# Block_Diagram.net
KiCad netlist of a schematic drawn in EAGLE
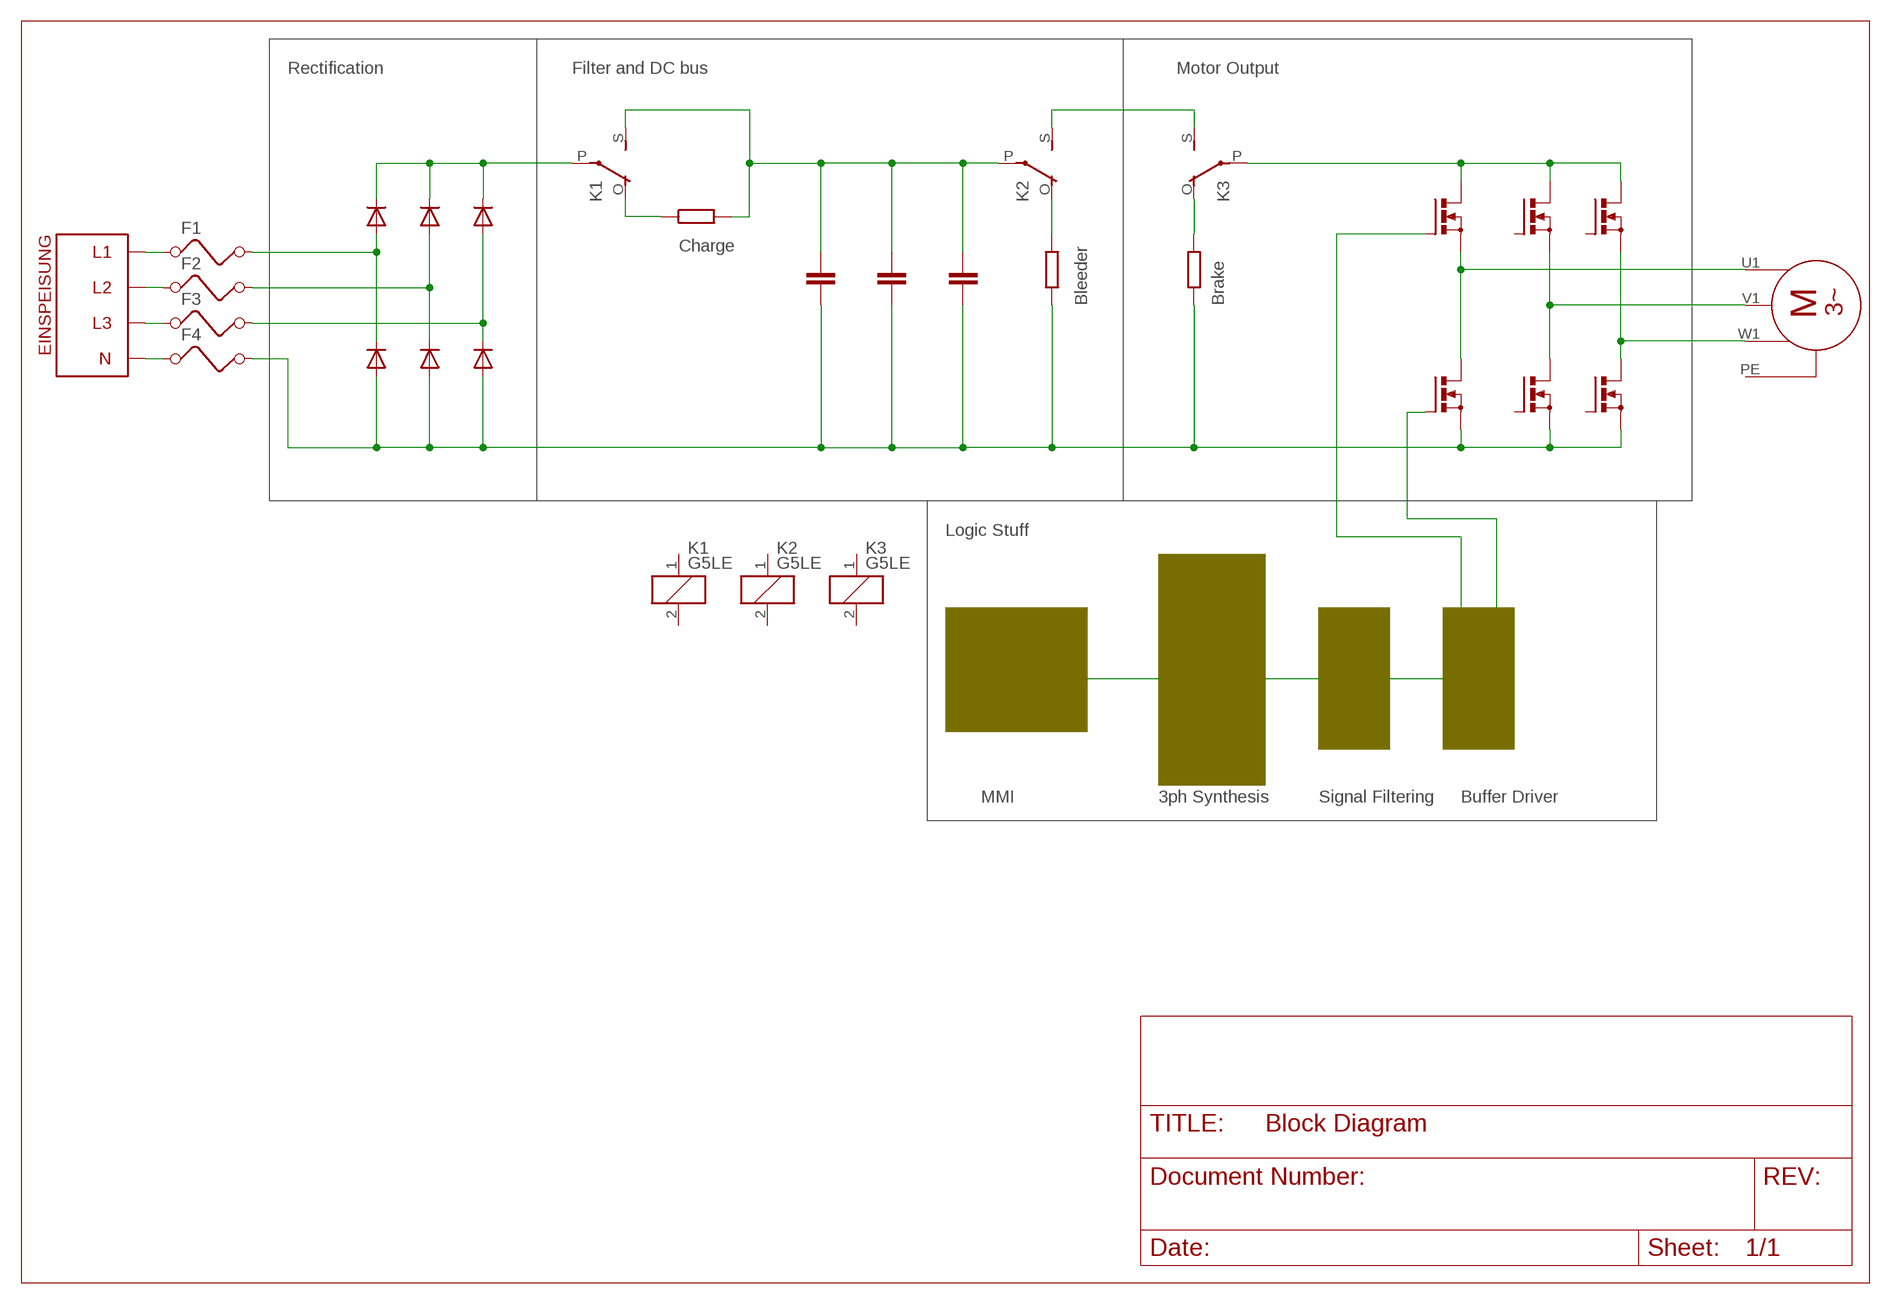
[diagram p0: schematic, sheet 1]

(export (version "E")
  (design (tool "Eeschema 10.0.6"))
  (components
    (comp (ref "F1")
      (value "FUSE")
      (footprint "eagle-import:FUSE")
      (libsource (lib "eagle-import") (part "FUSE"))
    )
    (comp (ref "F2")
      (value "FUSE")
      (footprint "eagle-import:FUSE")
      (libsource (lib "eagle-import") (part "FUSE"))
    )
    (comp (ref "F3")
      (value "FUSE")
      (footprint "eagle-import:FUSE")
      (libsource (lib "eagle-import") (part "FUSE"))
    )
    (comp (ref "F4")
      (value "FUSE")
      (footprint "eagle-import:FUSE")
      (libsource (lib "eagle-import") (part "FUSE"))
    )
    (comp (ref "K1")
      (value "G5LE")
      (footprint "eagle-import:G5LE")
      (libsource (lib "eagle-import") (part "G5LE"))
    )
    (comp (ref "K2")
      (value "G5LE")
      (footprint "eagle-import:G5LE")
      (libsource (lib "eagle-import") (part "G5LE"))
    )
    (comp (ref "K3")
      (value "G5LE")
      (footprint "eagle-import:G5LE")
      (libsource (lib "eagle-import") (part "G5LE"))
    )
    (comp (ref "M1")
      (value "MOTOR_3-POL_PE")
      (footprint "eagle-import:MOTOR_3-POL_PE")
      (libsource (lib "eagle-import") (part "MOTOR_3-POL_PE"))
    )
    (comp (ref "Q1")
      (value "IRF512")
      (footprint "eagle-import:TO220BV")
      (libsource (lib "eagle-import") (part "IRF512"))
    )
    (comp (ref "Q2")
      (value "IRF512")
      (footprint "eagle-import:TO220BV")
      (libsource (lib "eagle-import") (part "IRF512"))
    )
    (comp (ref "Q3")
      (value "IRF512")
      (footprint "eagle-import:TO220BV")
      (libsource (lib "eagle-import") (part "IRF512"))
    )
    (comp (ref "Q4")
      (value "IRF512")
      (footprint "eagle-import:TO220BV")
      (libsource (lib "eagle-import") (part "IRF512"))
    )
    (comp (ref "Q5")
      (value "IRF512")
      (footprint "eagle-import:TO220BV")
      (libsource (lib "eagle-import") (part "IRF512"))
    )
    (comp (ref "Q6")
      (value "IRF512")
      (footprint "eagle-import:TO220BV")
      (libsource (lib "eagle-import") (part "IRF512"))
    )
  )
  (nets
    (net (code "1") (name "Net-(F1-Pad1)") (class "Default")
      (node (ref "F1") (pin "1") (pinfunction "1_1") (pintype "passive"))
    )
    (net (code "2") (name "Net-(F2-Pad1)") (class "Default")
      (node (ref "F2") (pin "1") (pinfunction "1_1") (pintype "passive"))
    )
    (net (code "3") (name "Net-(F3-Pad1)") (class "Default")
      (node (ref "F3") (pin "1") (pinfunction "1_1") (pintype "passive"))
    )
    (net (code "4") (name "Net-(F4-Pad1)") (class "Default")
      (node (ref "F4") (pin "1") (pinfunction "1_1") (pintype "passive"))
    )
    (net (code "5") (name "Net-(F4-Pad2)") (class "Default")
      (node (ref "F4") (pin "2") (pinfunction "2_2") (pintype "passive"))
      (node (ref "Q4") (pin "S") (pinfunction "S_S") (pintype "passive"))
      (node (ref "Q5") (pin "S") (pinfunction "S_S") (pintype "passive"))
      (node (ref "Q6") (pin "S") (pinfunction "S_S") (pintype "passive"))
    )
    (net (code "6") (name "Net-(K1-PadS)") (class "Default")
      (node (ref "K1") (pin "S") (pinfunction "S_S") (pintype "passive"))
      (node (ref "K2") (pin "P") (pinfunction "P_P") (pintype "passive"))
    )
    (net (code "7") (name "Net-(K2-PadS)") (class "Default")
      (node (ref "K2") (pin "S") (pinfunction "S_S") (pintype "passive"))
      (node (ref "K3") (pin "S") (pinfunction "S_S") (pintype "passive"))
    )
    (net (code "8") (name "Net-(K3-PadP)") (class "Default")
      (node (ref "K3") (pin "P") (pinfunction "P_P") (pintype "passive"))
      (node (ref "Q1") (pin "D") (pinfunction "D_D") (pintype "passive"))
      (node (ref "Q2") (pin "D") (pinfunction "D_D") (pintype "passive"))
      (node (ref "Q3") (pin "D") (pinfunction "D_D") (pintype "passive"))
    )
    (net (code "9") (name "Net-(M1-PadU1)") (class "Default")
      (node (ref "M1") (pin "U1") (pinfunction "U1_U1") (pintype "passive"))
      (node (ref "Q1") (pin "S") (pinfunction "S_S") (pintype "passive"))
      (node (ref "Q6") (pin "D") (pinfunction "D_D") (pintype "passive"))
    )
    (net (code "10") (name "Net-(M1-PadV1)") (class "Default")
      (node (ref "M1") (pin "V1") (pinfunction "V1_V1") (pintype "passive"))
      (node (ref "Q2") (pin "S") (pinfunction "S_S") (pintype "passive"))
      (node (ref "Q5") (pin "D") (pinfunction "D_D") (pintype "passive"))
    )
    (net (code "11") (name "Net-(M1-PadW1)") (class "Default")
      (node (ref "M1") (pin "W1") (pinfunction "W1_W1") (pintype "passive"))
      (node (ref "Q3") (pin "S") (pinfunction "S_S") (pintype "passive"))
      (node (ref "Q4") (pin "D") (pinfunction "D_D") (pintype "passive"))
    )
    (net (code "12") (name "unconnected-(F1-Pad2)") (class "Default")
      (node (ref "F1") (pin "2") (pinfunction "2_2") (pintype "passive"))
    )
    (net (code "13") (name "unconnected-(F2-Pad2)") (class "Default")
      (node (ref "F2") (pin "2") (pinfunction "2_2") (pintype "passive"))
    )
    (net (code "14") (name "unconnected-(F3-Pad2)") (class "Default")
      (node (ref "F3") (pin "2") (pinfunction "2_2") (pintype "passive"))
    )
    (net (code "15") (name "unconnected-(K1-Pad1)") (class "Default")
      (node (ref "K1") (pin "1") (pinfunction "1_1") (pintype "passive"))
    )
    (net (code "16") (name "unconnected-(K1-Pad2)") (class "Default")
      (node (ref "K1") (pin "2") (pinfunction "2_2") (pintype "passive"))
    )
    (net (code "17") (name "unconnected-(K1-PadO)") (class "Default")
      (node (ref "K1") (pin "O") (pinfunction "O_O") (pintype "passive"))
    )
    (net (code "18") (name "unconnected-(K1-PadP)") (class "Default")
      (node (ref "K1") (pin "P") (pinfunction "P_P") (pintype "passive"))
    )
    (net (code "19") (name "unconnected-(K2-Pad1)") (class "Default")
      (node (ref "K2") (pin "1") (pinfunction "1_1") (pintype "passive"))
    )
    (net (code "20") (name "unconnected-(K2-Pad2)") (class "Default")
      (node (ref "K2") (pin "2") (pinfunction "2_2") (pintype "passive"))
    )
    (net (code "21") (name "unconnected-(K2-PadO)") (class "Default")
      (node (ref "K2") (pin "O") (pinfunction "O_O") (pintype "passive"))
    )
    (net (code "22") (name "unconnected-(K3-Pad1)") (class "Default")
      (node (ref "K3") (pin "1") (pinfunction "1_1") (pintype "passive"))
    )
    (net (code "23") (name "unconnected-(K3-Pad2)") (class "Default")
      (node (ref "K3") (pin "2") (pinfunction "2_2") (pintype "passive"))
    )
    (net (code "24") (name "unconnected-(K3-PadO)") (class "Default")
      (node (ref "K3") (pin "O") (pinfunction "O_O") (pintype "passive"))
    )
    (net (code "25") (name "unconnected-(M1-PadPE)") (class "Default")
      (node (ref "M1") (pin "PE") (pinfunction "PE_PE") (pintype "passive"))
    )
    (net (code "26") (name "unconnected-(Q1-PadG)") (class "Default")
      (node (ref "Q1") (pin "G") (pinfunction "G_G") (pintype "passive"))
    )
    (net (code "27") (name "unconnected-(Q2-PadG)") (class "Default")
      (node (ref "Q2") (pin "G") (pinfunction "G_G") (pintype "passive"))
    )
    (net (code "28") (name "unconnected-(Q3-PadG)") (class "Default")
      (node (ref "Q3") (pin "G") (pinfunction "G_G") (pintype "passive"))
    )
    (net (code "29") (name "unconnected-(Q4-PadG)") (class "Default")
      (node (ref "Q4") (pin "G") (pinfunction "G_G") (pintype "passive"))
    )
    (net (code "30") (name "unconnected-(Q5-PadG)") (class "Default")
      (node (ref "Q5") (pin "G") (pinfunction "G_G") (pintype "passive"))
    )
    (net (code "31") (name "unconnected-(Q6-PadG)") (class "Default")
      (node (ref "Q6") (pin "G") (pinfunction "G_G") (pintype "passive"))
    )
  )
)
